# Manuel_Wake-up_and_Latch.net
KiCad netlist of a schematic drawn in Altium Designer
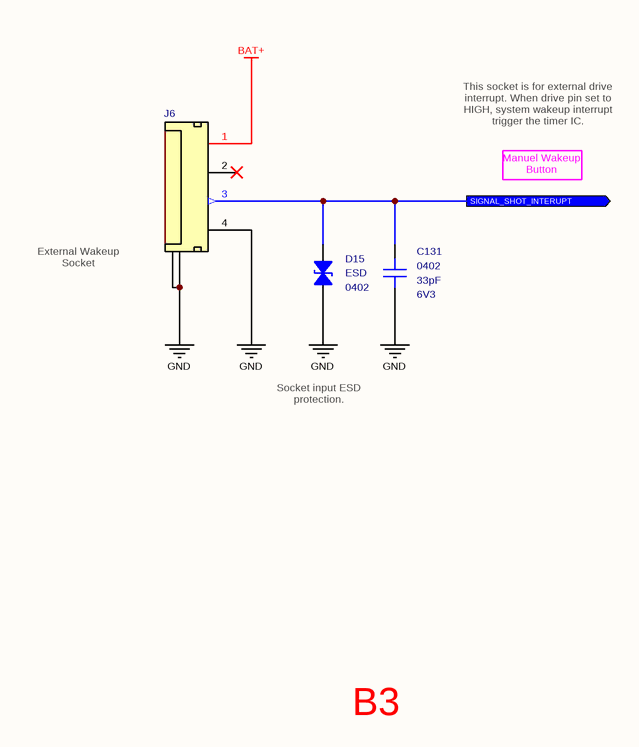
[diagram p0: Manuel Wake-up and Latch.SchDoc]

(export (version "E")
  (design (tool "Eeschema 10.0.6"))
  (components
    (comp (ref "C131")
      (value "33pF")
      (footprint "CAPACITOR_0402")
      (description "Capacitor - 33pF [0402] (Ceramic)")
      (fields
        (field (name "MANUFACTURER_PART_NUMBER") "C0402C330J9RACAUTO")
        (field (name "MOUSER_PART_NUMBER") "80-C0402C330J9RAUTO")
        (field (name "CASE") "0402")
        (field (name "VOLTAGE") "6V3")
      )
      (libsource (lib "Ovoo_Schematic") (part "Capacitor - 33pF [0402-6V3]"))
    )
    (comp (ref "D15")
      (value "ESD Suppressors")
      (footprint "ESD_0402")
      (description "TVS Diode (Bi-directional)")
      (fields
        (field (name "MANUFACTURER_PART_NUMBER") "0402ESDA-MLP1")
        (field (name "MOUSER_PART_NUMBER") "504-0402ESDA-MLP1")
        (field (name "CASE") "0402")
      )
      (libsource (lib "Ovoo_Schematic") (part "Diode - ESD Protection"))
    )
    (comp (ref "J6")
      (value "4P SMD Tunic Connector")
      (footprint "Connector_Tunic 4P - H")
      (description "Mini Tunic Connector with 4P")
      (fields
        (field (name "MANUFACTURER_PART_NUMBER") "53261-0471")
        (field (name "MOUSER_PART_NUMBER") "538-53261-0471")
      )
      (libsource (lib "Ovoo_Schematic") (part "Connector - Mini Tunic 4P (1.25)"))
    )
  )
  (nets
    (net (code "1") (name "/SIGNAL_SHOT_INTERUPT") (class "Default")
      (node (ref "C131") (pin "2") (pinfunction "2_2") (pintype "passive"))
      (node (ref "D15") (pin "2") (pinfunction "2_2") (pintype "passive"))
      (node (ref "J6") (pin "3") (pinfunction "Button_3") (pintype "output"))
    )
    (net (code "2") (name "BAT+") (class "Default")
      (node (ref "J6") (pin "1") (pinfunction "BAT+_1") (pintype "power_in"))
    )
    (net (code "3") (name "GND") (class "Default")
      (node (ref "C131") (pin "1") (pinfunction "1_1") (pintype "passive"))
      (node (ref "D15") (pin "1") (pinfunction "1_1") (pintype "passive"))
      (node (ref "J6") (pin "4") (pinfunction "GND_4") (pintype "power_in"))
      (node (ref "J6") (pin "5") (pinfunction "Termination_5") (pintype "passive"))
      (node (ref "J6") (pin "6") (pinfunction "Termination_6") (pintype "passive"))
    )
    (net (code "4") (name "unconnected-(J6-NC-Pad2)") (class "Default")
      (node (ref "J6") (pin "2") (pinfunction "NC_2") (pintype "passive+no_connect"))
    )
  )
)
